# LEDs.net
KiCad netlist of a schematic drawn in Altium Designer
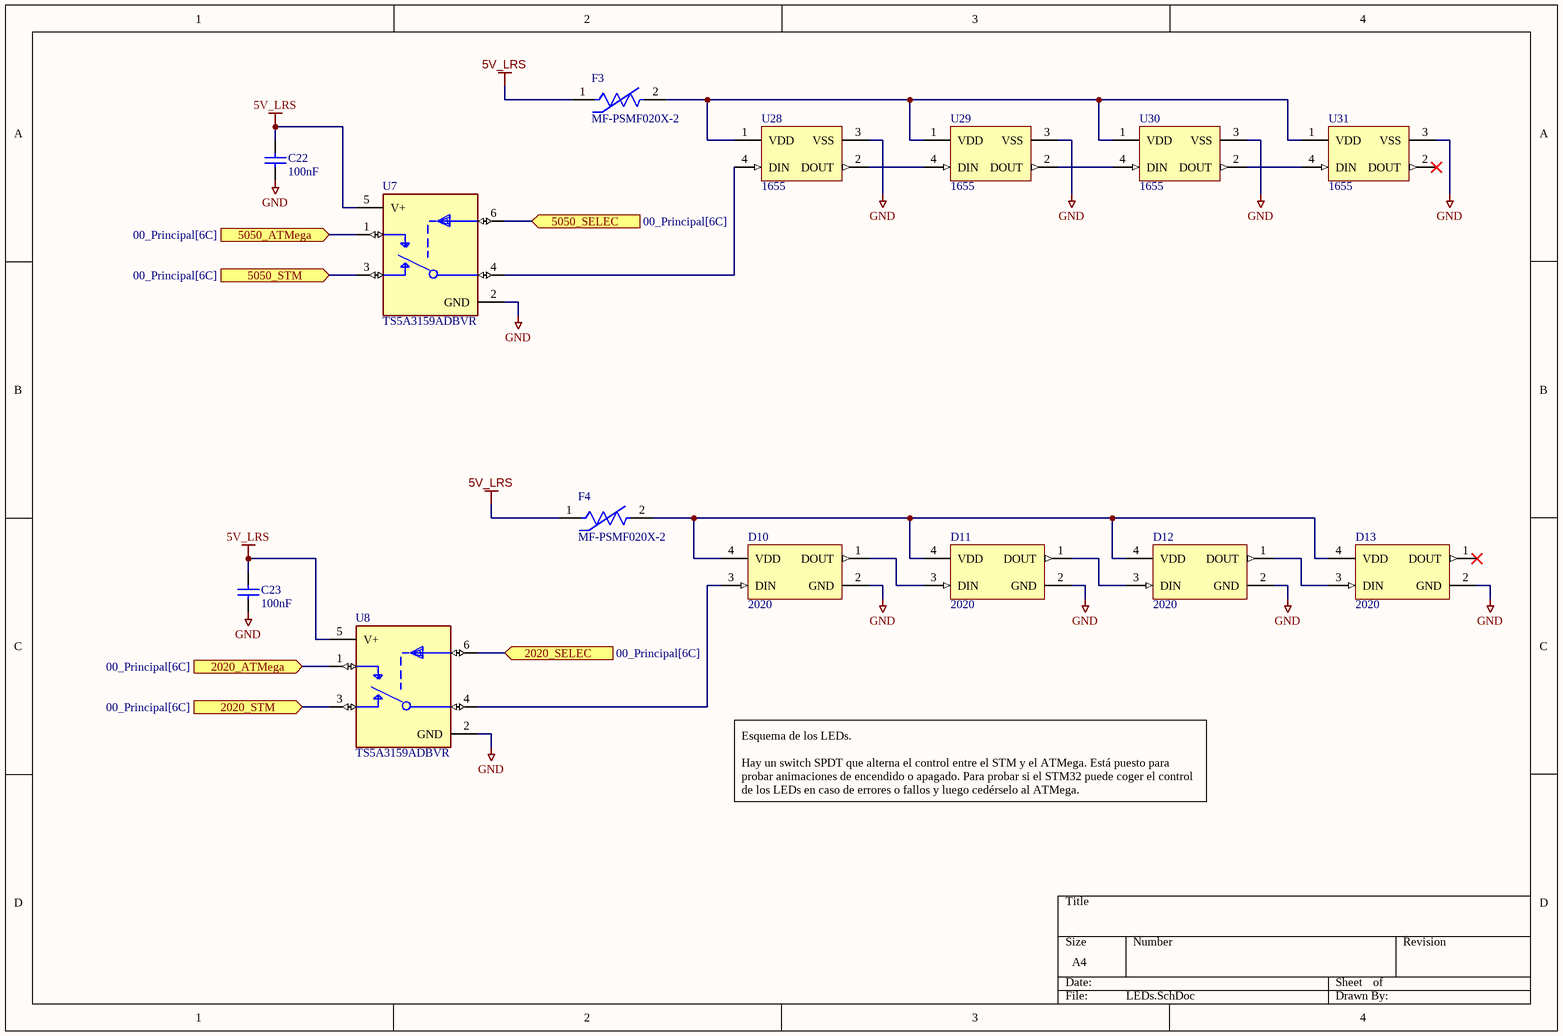
[diagram p0: LEDs.SchDoc]

(export (version "E")
  (design (tool "Eeschema 10.0.6"))
  (components
    (comp (ref "C22")
      (value "100nF")
      (footprint "CAPC1005X55X25NL05T05")
      (fields (field (name "MANUFACTURER") "Vitramon") (field (name "PART NUMBER") "VJ0402Y104KXJCW1BC"))
      (libsource (lib "Altium Content Vault") (part "CAP"))
    )
    (comp (ref "C23")
      (value "100nF")
      (footprint "CAPC1005X55X25NL05T05")
      (fields (field (name "MANUFACTURER") "Vitramon") (field (name "PART NUMBER") "VJ0402Y104KXJCW1BC"))
      (libsource (lib "Altium Content Vault") (part "CAP"))
    )
    (comp (ref "D10")
      (value "2020")
      (footprint "Adafruit 4684")
      (description "Adafruit Accessories NeoPixel Nano 2020 RGB LEDs WS2812B")
      (libsource (lib "Esquemas") (part "NeoPixel Nano 2020"))
    )
    (comp (ref "D11")
      (value "2020")
      (footprint "Adafruit 4684")
      (description "Adafruit Accessories NeoPixel Nano 2020 RGB LEDs WS2812B")
      (libsource (lib "Esquemas") (part "NeoPixel Nano 2020"))
    )
    (comp (ref "D12")
      (value "2020")
      (footprint "Adafruit 4684")
      (description "Adafruit Accessories NeoPixel Nano 2020 RGB LEDs WS2812B")
      (libsource (lib "Esquemas") (part "NeoPixel Nano 2020"))
    )
    (comp (ref "D13")
      (value "2020")
      (footprint "Adafruit 4684")
      (description "Adafruit Accessories NeoPixel Nano 2020 RGB LEDs WS2812B")
      (libsource (lib "Esquemas") (part "NeoPixel Nano 2020"))
    )
    (comp (ref "F3")
      (value "MF-PSMF020X-2")
      (footprint "FP-MF-PSMF-MFG")
      (description "PTC RESET FUSE 9V 200MA 0805")
      (fields
        (field (name "MANUFACTURER") "Bourns")
        (field (name "OCTOPART") "https://octopart.com/mf-psmf020x-2-bourns-7483437")
      )
      (libsource (lib "Altium Content Vault") (part "3b148a6ebabc5fb4d708a66c052d352"))
    )
    (comp (ref "F4")
      (value "MF-PSMF020X-2")
      (footprint "FP-MF-PSMF-MFG")
      (description "PTC RESET FUSE 9V 200MA 0805")
      (fields
        (field (name "MANUFACTURER") "Bourns")
        (field (name "OCTOPART") "https://octopart.com/mf-psmf020x-2-bourns-7483437")
      )
      (libsource (lib "Altium Content Vault") (part "3b148a6ebabc5fb4d708a66c052d352"))
    )
    (comp (ref "U7")
      (value "TS5A3159ADBVR")
      (footprint "FP-DBV0006A-MFG")
      (description "IC SWITCH SPDT SOT23-6")
      (fields
        (field (name "OCTOPART") "https://octopart.com/ts5a3159adbvr-texas+instruments-443714")
        (field (name "MANUFACTURER") "Texas Instruments")
      )
      (libsource (lib "Altium Content Vault") (part "c774ca8c69cedcd98454b34721cea07"))
    )
    (comp (ref "U8")
      (value "TS5A3159ADBVR")
      (footprint "FP-DBV0006A-MFG")
      (description "IC SWITCH SPDT SOT23-6")
      (fields
        (field (name "OCTOPART") "https://octopart.com/ts5a3159adbvr-texas+instruments-443714")
        (field (name "MANUFACTURER") "Texas Instruments")
      )
      (libsource (lib "Altium Content Vault") (part "c774ca8c69cedcd98454b34721cea07"))
    )
    (comp (ref "U28")
      (value "1655")
      (footprint "ADA-RGB-1655_V")
      (fields (field (name "MANUFACTURER") "Adafruit-Industries-LLC"))
      (libsource (lib "Altium Content Vault") (part "ADA-RGB-1655-4"))
    )
    (comp (ref "U29")
      (value "1655")
      (footprint "ADA-RGB-1655_V")
      (fields (field (name "MANUFACTURER") "Adafruit-Industries-LLC"))
      (libsource (lib "Altium Content Vault") (part "ADA-RGB-1655-4"))
    )
    (comp (ref "U30")
      (value "1655")
      (footprint "ADA-RGB-1655_V")
      (fields (field (name "MANUFACTURER") "Adafruit-Industries-LLC"))
      (libsource (lib "Altium Content Vault") (part "ADA-RGB-1655-4"))
    )
    (comp (ref "U31")
      (value "1655")
      (footprint "ADA-RGB-1655_V")
      (fields (field (name "MANUFACTURER") "Adafruit-Industries-LLC"))
      (libsource (lib "Altium Content Vault") (part "ADA-RGB-1655-4"))
    )
  )
  (nets
    (net (code "1") (name "/2020_ATMega") (class "Default")
      (node (ref "U8") (pin "1") (pinfunction "NO_1") (pintype "bidirectional"))
    )
    (net (code "2") (name "/2020_SELEC") (class "Default")
      (node (ref "U8") (pin "6") (pinfunction "IN_6") (pintype "bidirectional"))
    )
    (net (code "3") (name "/2020_STM") (class "Default")
      (node (ref "U8") (pin "3") (pinfunction "NC_3") (pintype "bidirectional"))
    )
    (net (code "4") (name "/5050_ATMega") (class "Default")
      (node (ref "U7") (pin "1") (pinfunction "NO_1") (pintype "bidirectional"))
    )
    (net (code "5") (name "/5050_SELEC") (class "Default")
      (node (ref "U7") (pin "6") (pinfunction "IN_6") (pintype "bidirectional"))
    )
    (net (code "6") (name "/5050_STM") (class "Default")
      (node (ref "U7") (pin "3") (pinfunction "NC_3") (pintype "bidirectional"))
    )
    (net (code "7") (name "5V_LRS") (class "Default")
      (node (ref "C22") (pin "2") (pinfunction "2_2") (pintype "passive"))
      (node (ref "C23") (pin "2") (pinfunction "2_2") (pintype "passive"))
      (node (ref "F3") (pin "1") (pinfunction "1_1") (pintype "passive"))
      (node (ref "F4") (pin "1") (pinfunction "1_1") (pintype "passive"))
      (node (ref "U7") (pin "5") (pinfunction "V+_5") (pintype "power_in"))
      (node (ref "U8") (pin "5") (pinfunction "V+_5") (pintype "power_in"))
    )
    (net (code "8") (name "GND") (class "Default")
      (node (ref "C22") (pin "1") (pinfunction "1_1") (pintype "passive"))
      (node (ref "C23") (pin "1") (pinfunction "1_1") (pintype "passive"))
      (node (ref "D10") (pin "2") (pinfunction "GND_2") (pintype "passive"))
      (node (ref "D11") (pin "2") (pinfunction "GND_2") (pintype "passive"))
      (node (ref "D12") (pin "2") (pinfunction "GND_2") (pintype "passive"))
      (node (ref "D13") (pin "2") (pinfunction "GND_2") (pintype "passive"))
      (node (ref "U28") (pin "3") (pinfunction "VSS_3") (pintype "power_in"))
      (node (ref "U29") (pin "3") (pinfunction "VSS_3") (pintype "power_in"))
      (node (ref "U30") (pin "3") (pinfunction "VSS_3") (pintype "power_in"))
      (node (ref "U31") (pin "3") (pinfunction "VSS_3") (pintype "power_in"))
      (node (ref "U7") (pin "2") (pinfunction "GND_2") (pintype "power_in"))
      (node (ref "U8") (pin "2") (pinfunction "GND_2") (pintype "power_in"))
    )
    (net (code "9") (name "Net-(D10-DIN)") (class "Default")
      (node (ref "D10") (pin "3") (pinfunction "DIN_3") (pintype "input"))
      (node (ref "U8") (pin "4") (pinfunction "COM_4") (pintype "bidirectional"))
    )
    (net (code "10") (name "Net-(D10-DOUT)") (class "Default")
      (node (ref "D10") (pin "1") (pinfunction "DOUT_1") (pintype "output"))
      (node (ref "D11") (pin "3") (pinfunction "DIN_3") (pintype "input"))
    )
    (net (code "11") (name "Net-(D10-VDD)") (class "Default")
      (node (ref "D10") (pin "4") (pinfunction "VDD_4") (pintype "passive"))
      (node (ref "D11") (pin "4") (pinfunction "VDD_4") (pintype "passive"))
      (node (ref "D12") (pin "4") (pinfunction "VDD_4") (pintype "passive"))
      (node (ref "D13") (pin "4") (pinfunction "VDD_4") (pintype "passive"))
      (node (ref "F4") (pin "2") (pinfunction "2_2") (pintype "passive"))
    )
    (net (code "12") (name "Net-(D11-DOUT)") (class "Default")
      (node (ref "D11") (pin "1") (pinfunction "DOUT_1") (pintype "output"))
      (node (ref "D12") (pin "3") (pinfunction "DIN_3") (pintype "input"))
    )
    (net (code "13") (name "Net-(D12-DOUT)") (class "Default")
      (node (ref "D12") (pin "1") (pinfunction "DOUT_1") (pintype "output"))
      (node (ref "D13") (pin "3") (pinfunction "DIN_3") (pintype "input"))
    )
    (net (code "14") (name "Net-(U28-DIN)") (class "Default")
      (node (ref "U28") (pin "4") (pinfunction "DIN_4") (pintype "input"))
      (node (ref "U7") (pin "4") (pinfunction "COM_4") (pintype "bidirectional"))
    )
    (net (code "15") (name "Net-(U28-DOUT)") (class "Default")
      (node (ref "U28") (pin "2") (pinfunction "DOUT_2") (pintype "output"))
      (node (ref "U29") (pin "4") (pinfunction "DIN_4") (pintype "input"))
    )
    (net (code "16") (name "Net-(U28-VDD)") (class "Default")
      (node (ref "F3") (pin "2") (pinfunction "2_2") (pintype "passive"))
      (node (ref "U28") (pin "1") (pinfunction "VDD_1") (pintype "power_in"))
      (node (ref "U29") (pin "1") (pinfunction "VDD_1") (pintype "power_in"))
      (node (ref "U30") (pin "1") (pinfunction "VDD_1") (pintype "power_in"))
      (node (ref "U31") (pin "1") (pinfunction "VDD_1") (pintype "power_in"))
    )
    (net (code "17") (name "Net-(U29-DOUT)") (class "Default")
      (node (ref "U29") (pin "2") (pinfunction "DOUT_2") (pintype "output"))
      (node (ref "U30") (pin "4") (pinfunction "DIN_4") (pintype "input"))
    )
    (net (code "18") (name "Net-(U30-DOUT)") (class "Default")
      (node (ref "U30") (pin "2") (pinfunction "DOUT_2") (pintype "output"))
      (node (ref "U31") (pin "4") (pinfunction "DIN_4") (pintype "input"))
    )
    (net (code "19") (name "unconnected-(D13-DOUT-Pad1)") (class "Default")
      (node (ref "D13") (pin "1") (pinfunction "DOUT_1") (pintype "output+no_connect"))
    )
    (net (code "20") (name "unconnected-(U31-DOUT-Pad2)") (class "Default")
      (node (ref "U31") (pin "2") (pinfunction "DOUT_2") (pintype "output+no_connect"))
    )
  )
)
